# Sheet2.net
KiCad netlist of a schematic drawn in Altium Designer
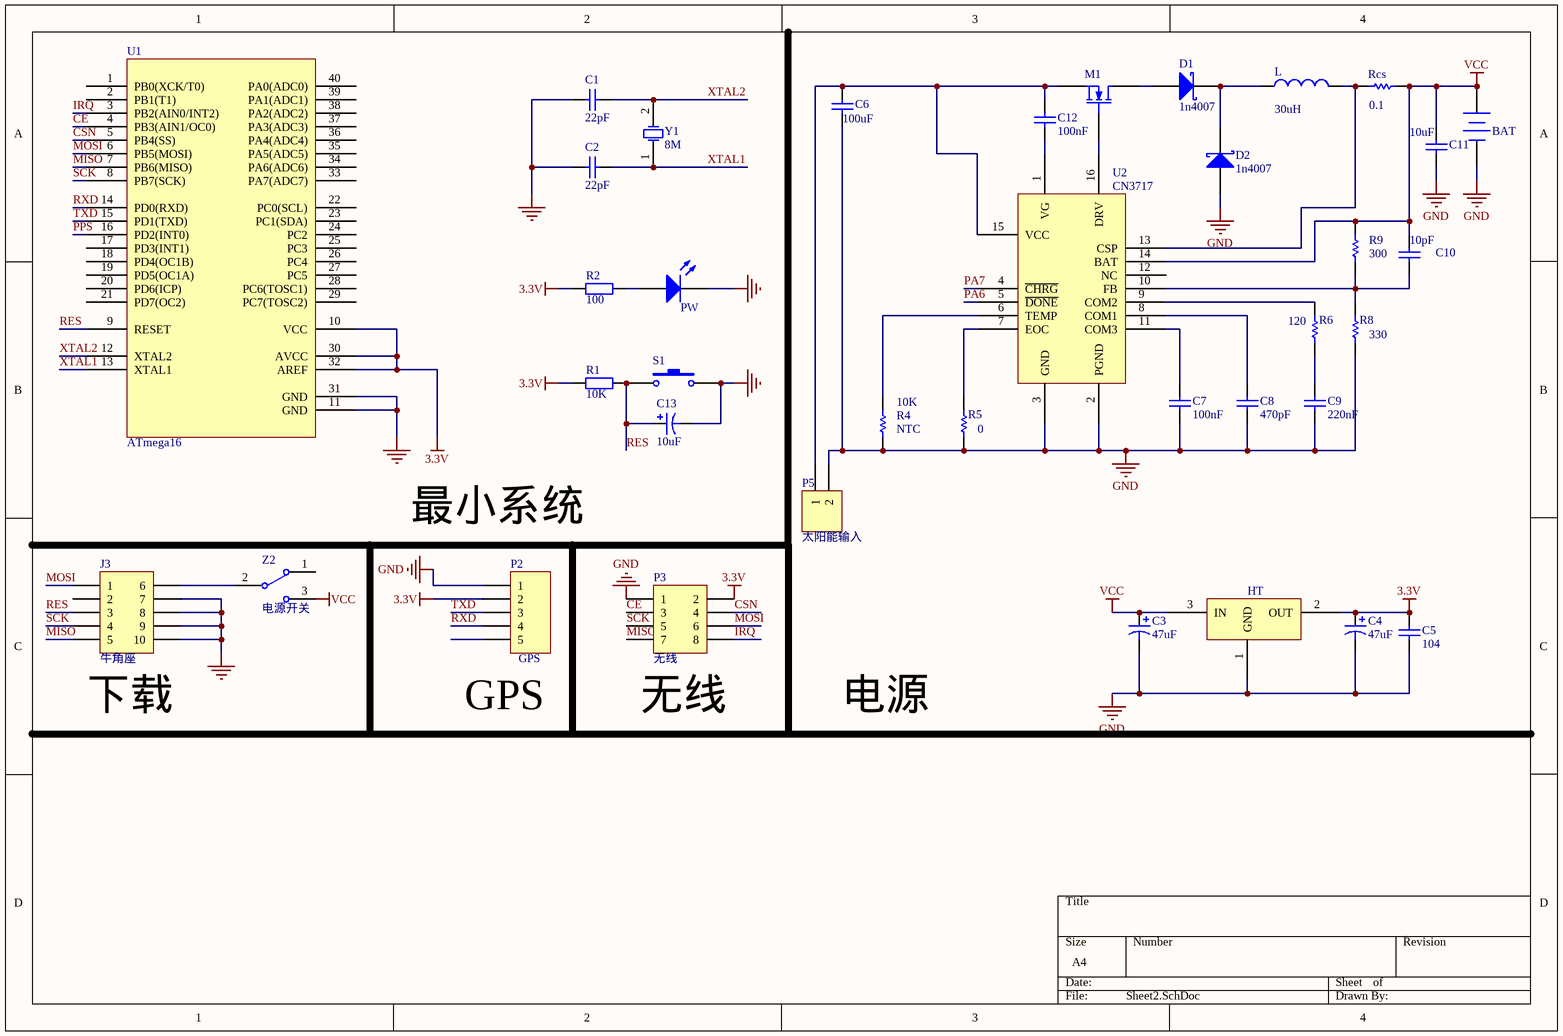
[diagram p0: Sheet2.SchDoc]

(export (version "E")
  (design (tool "Eeschema 10.0.6"))
  (components
    (comp (ref "1117_3.3V")
      (value "HT")
      (footprint "AMS1117-3.3V  SOT-223  贴片")
      (libsource (lib "Schlib1") (part "Component_1"))
    )
    (comp (ref "BAT")
      (value "Battery")
      (footprint "大2端子")
      (description "Multicell Battery")
      (fields (field (name "PUBLISHER") "Altium Limited"))
      (libsource (lib "Miscellaneous Devices") (part "Battery"))
    )
    (comp (ref "C1")
      (value "22pF")
      (footprint "电容CBB224(0.22)")
      (description "Capacitor")
      (fields (field (name "PUBLISHER") "Altium Limited"))
      (libsource (lib "Miscellaneous Devices") (part "Cap"))
    )
    (comp (ref "C2")
      (value "22pF")
      (footprint "电容CBB224(0.22)")
      (description "Capacitor")
      (fields (field (name "PUBLISHER") "Altium Limited"))
      (libsource (lib "Miscellaneous Devices") (part "Cap"))
    )
    (comp (ref "C3")
      (value "47uF")
      (footprint "电容")
      (description "Polarized Capacitor (Surface Mount)")
      (fields (field (name "PUBLISHER") "Altium Limited"))
      (libsource (lib "Miscellaneous Devices") (part "Cap Pol3"))
    )
    (comp (ref "C4")
      (value "47uF")
      (footprint "电容")
      (description "Polarized Capacitor (Surface Mount)")
      (fields (field (name "PUBLISHER") "Altium Limited"))
      (libsource (lib "Miscellaneous Devices") (part "Cap Pol3"))
    )
    (comp (ref "C5")
      (value "104")
      (footprint "电容CBB224(0.22)")
      (description "Capacitor")
      (fields (field (name "Comment") "Cap") (field (name "PUBLISHER") "Altium Limited"))
      (libsource (lib "Miscellaneous Devices") (part "Cap"))
    )
    (comp (ref "C6")
      (value "100uF")
      (footprint "电容CBB224(0.22)")
      (description "Capacitor")
      (fields (field (name "Comment") "Cap") (field (name "PUBLISHER") "Altium Limited"))
      (libsource (lib "Miscellaneous Devices") (part "Cap"))
    )
    (comp (ref "C7")
      (value "100nF")
      (footprint "电容CBB224(0.22)")
      (description "Capacitor")
      (fields (field (name "Comment") "Cap") (field (name "PUBLISHER") "Altium Limited"))
      (libsource (lib "Miscellaneous Devices") (part "Cap"))
    )
    (comp (ref "C8")
      (value "470pF")
      (footprint "电容CBB224(0.22)")
      (description "Capacitor")
      (fields (field (name "Comment") "Cap") (field (name "PUBLISHER") "Altium Limited"))
      (libsource (lib "Miscellaneous Devices") (part "Cap"))
    )
    (comp (ref "C9")
      (value "220nF")
      (footprint "电容CBB224(0.22)")
      (description "Capacitor")
      (fields (field (name "Comment") "Cap") (field (name "PUBLISHER") "Altium Limited"))
      (libsource (lib "Miscellaneous Devices") (part "Cap"))
    )
    (comp (ref "C10")
      (value "10pF")
      (footprint "电容CBB224(0.22)")
      (description "Capacitor")
      (fields (field (name "Comment") "Cap") (field (name "PUBLISHER") "Altium Limited"))
      (libsource (lib "Miscellaneous Devices") (part "Cap"))
    )
    (comp (ref "C11")
      (value "10uF")
      (footprint "电容CBB224(0.22)")
      (description "Capacitor")
      (fields (field (name "Comment") "Cap") (field (name "PUBLISHER") "Altium Limited"))
      (libsource (lib "Miscellaneous Devices") (part "Cap"))
    )
    (comp (ref "C12")
      (value "100nF")
      (footprint "电容CBB224(0.22)")
      (description "Capacitor")
      (fields (field (name "Comment") "Cap") (field (name "PUBLISHER") "Altium Limited"))
      (libsource (lib "Miscellaneous Devices") (part "Cap"))
    )
    (comp (ref "C13")
      (value "10uF")
      (footprint "电容")
      (description "Polarized Capacitor (Surface Mount)")
      (fields (field (name "PUBLISHER") "Altium Limited"))
      (libsource (lib "Miscellaneous Devices") (part "Cap Pol3"))
    )
    (comp (ref "D1")
      (value "1n4007")
      (footprint "稳压二极管")
      (description "Schottky Diode")
      (fields (field (name "PUBLISHER") "Altium Limited"))
      (libsource (lib "Miscellaneous Devices") (part "D Schottky"))
    )
    (comp (ref "D2")
      (value "1n4007")
      (footprint "稳压二极管")
      (description "Schottky Diode")
      (fields (field (name "PUBLISHER") "Altium Limited"))
      (libsource (lib "Miscellaneous Devices") (part "D Schottky"))
    )
    (comp (ref "J3")
      (value "牛角座")
      (footprint "下载口（12345）")
      (description "Header, 5-Pin, Dual row")
      (fields (field (name "PUBLISHER") "Altium Limited"))
      (libsource (lib "Miscellaneous Connectors") (part "Header 5X2A"))
    )
    (comp (ref "L")
      (value "30uH")
      (footprint "电感 直插")
      (description "Inductor")
      (fields (field (name "PUBLISHER") "Altium Limited"))
      (libsource (lib "Miscellaneous Devices") (part "Inductor"))
    )
    (comp (ref "M1")
      (value "MOSFET-N")
      (footprint "MOS管 贴片")
      (description "N-Channel MOSFET")
      (fields (field (name "PUBLISHER") "Altium Limited"))
      (libsource (lib "Miscellaneous Devices") (part "MOSFET-N"))
    )
    (comp (ref "P2")
      (value "GPS")
      (footprint "GPS模块")
      (description "Header, 5-Pin")
      (fields (field (name "PUBLISHER") "Altium Limited"))
      (libsource (lib "Miscellaneous Connectors") (part "Header 5"))
    )
    (comp (ref "P3")
      (value "无线")
      (footprint "无线模块")
      (description "Header, 4-Pin, Dual row")
      (fields (field (name "PUBLISHER") "Altium Limited"))
      (libsource (lib "Miscellaneous Connectors") (part "Header 4X2"))
    )
    (comp (ref "P5")
      (value "太阳能输入")
      (footprint "大2端子")
      (description "Header, 2-Pin")
      (fields (field (name "PUBLISHER") "Altium Limited"))
      (libsource (lib "Miscellaneous Connectors") (part "Header 2"))
    )
    (comp (ref "PW")
      (value "~")
      (footprint "LED")
      (description "Typical INFRARED GaAs LED")
      (fields (field (name "PUBLISHER") "Altium Limited"))
      (libsource (lib "Miscellaneous Devices") (part "LED0"))
    )
    (comp (ref "R1")
      (value "10K")
      (footprint "0805")
      (description "Resistor")
      (fields (field (name "PUBLISHER") "Altium Limited"))
      (libsource (lib "Miscellaneous Devices") (part "Res2"))
    )
    (comp (ref "R2")
      (value "100")
      (footprint "0805")
      (description "Resistor")
      (fields (field (name "PUBLISHER") "Altium Limited"))
      (libsource (lib "Miscellaneous Devices") (part "Res2"))
    )
    (comp (ref "R4")
      (value "NTC")
      (footprint "1206")
      (description "Resistor")
      (fields (field (name "ALTIUM_VALUE") "10K") (field (name "PUBLISHER") "Altium Limited"))
      (libsource (lib "Miscellaneous Devices") (part "Res1"))
    )
    (comp (ref "R5")
      (value "0")
      (footprint "1206")
      (description "Resistor")
      (fields (field (name "Comment") "Res1") (field (name "PUBLISHER") "Altium Limited"))
      (libsource (lib "Miscellaneous Devices") (part "Res1"))
    )
    (comp (ref "R6")
      (value "120")
      (footprint "0805")
      (description "Resistor")
      (fields (field (name "Comment") "Res1") (field (name "PUBLISHER") "Altium Limited"))
      (libsource (lib "Miscellaneous Devices") (part "Res1"))
    )
    (comp (ref "R8")
      (value "330")
      (footprint "0805")
      (description "Resistor")
      (fields (field (name "Comment") "Res1") (field (name "PUBLISHER") "Altium Limited"))
      (libsource (lib "Miscellaneous Devices") (part "Res1"))
    )
    (comp (ref "R9")
      (value "300")
      (footprint "0805")
      (description "Resistor")
      (fields (field (name "Comment") "Res1") (field (name "PUBLISHER") "Altium Limited"))
      (libsource (lib "Miscellaneous Devices") (part "Res1"))
    )
    (comp (ref "Rcs")
      (value "0.1")
      (footprint "2512 贴片")
      (description "Resistor")
      (fields (field (name "Comment") "Res1") (field (name "PUBLISHER") "Altium Limited"))
      (libsource (lib "Miscellaneous Devices") (part "Res1"))
    )
    (comp (ref "S1")
      (value "~")
      (footprint "4脚按键")
      (description "Switch")
      (fields (field (name "PUBLISHER") "Altium Limited"))
      (libsource (lib "Miscellaneous Devices") (part "SW-PB"))
    )
    (comp (ref "U1")
      (value "ATmega16")
      (footprint "DIP 40 单片机")
      (libsource (lib "Schlib1") (part "Component_2"))
    )
    (comp (ref "U2") (value "CN3717") (footprint "CN3717 贴片") (libsource (lib "Schlib1") (part "CN3717")))
    (comp (ref "Y1")
      (value "8M")
      (footprint "晶振")
      (description "Crystal Oscillator")
      (fields (field (name "PUBLISHER") "Altium Limited"))
      (libsource (lib "Miscellaneous Devices") (part "XTAL"))
    )
    (comp (ref "Z2")
      (value "电源开关")
      (footprint "自锁开关")
      (description "SPDT Subminiature Toggle Switch, Right Angle Mounting, Vertical Actuation")
      (fields (field (name "PUBLISHER") "Altium Limited"))
      (libsource (lib "Miscellaneous Devices") (part "SW-SPDT"))
    )
  )
  (nets
    (net (code "1") (name "/CE") (class "Default")
      (node (ref "P3") (pin "3") (pinfunction "3_3") (pintype "passive"))
      (node (ref "U1") (pin "4") (pinfunction "PB3(AIN1/OC0)_4") (pintype "passive"))
    )
    (net (code "2") (name "/CSN") (class "Default")
      (node (ref "P3") (pin "4") (pinfunction "4_4") (pintype "passive"))
      (node (ref "U1") (pin "5") (pinfunction "PB4(SS)_5") (pintype "passive"))
    )
    (net (code "3") (name "/IRQ") (class "Default")
      (node (ref "P3") (pin "8") (pinfunction "8_8") (pintype "passive"))
      (node (ref "U1") (pin "3") (pinfunction "PB2(AIN0/INT2)_3") (pintype "passive"))
    )
    (net (code "4") (name "/MISO") (class "Default")
      (node (ref "J3") (pin "5") (pinfunction "5_5") (pintype "passive"))
      (node (ref "P3") (pin "7") (pinfunction "7_7") (pintype "passive"))
      (node (ref "U1") (pin "7") (pinfunction "PB6(MISO)_7") (pintype "passive"))
    )
    (net (code "5") (name "/MOSI") (class "Default")
      (node (ref "J3") (pin "1") (pinfunction "1_1") (pintype "passive"))
      (node (ref "P3") (pin "6") (pinfunction "6_6") (pintype "passive"))
      (node (ref "U1") (pin "6") (pinfunction "PB5(MOSI)_6") (pintype "passive"))
    )
    (net (code "6") (name "/PA6") (class "Default")
      (node (ref "U2") (pin "5") (pinfunction "~{DONE}_5") (pintype "passive"))
    )
    (net (code "7") (name "/PA7") (class "Default")
      (node (ref "U2") (pin "4") (pinfunction "~{CHRG}_4") (pintype "passive"))
    )
    (net (code "8") (name "/PPS") (class "Default")
      (node (ref "U1") (pin "16") (pinfunction "PD2(INT0)_16") (pintype "passive"))
    )
    (net (code "9") (name "/RES") (class "Default")
      (node (ref "C13") (pin "1") (pinfunction "1_1") (pintype "passive"))
      (node (ref "J3") (pin "3") (pinfunction "3_3") (pintype "passive"))
      (node (ref "R1") (pin "2") (pinfunction "2_2") (pintype "passive"))
      (node (ref "S1") (pin "1") (pinfunction "1_1") (pintype "passive"))
      (node (ref "U1") (pin "9") (pinfunction "RESET_9") (pintype "passive"))
    )
    (net (code "10") (name "/RXD") (class "Default")
      (node (ref "P2") (pin "4") (pinfunction "4_4") (pintype "passive"))
      (node (ref "U1") (pin "14") (pinfunction "PD0(RXD)_14") (pintype "passive"))
    )
    (net (code "11") (name "/SCK") (class "Default")
      (node (ref "J3") (pin "4") (pinfunction "4_4") (pintype "passive"))
      (node (ref "P3") (pin "5") (pinfunction "5_5") (pintype "passive"))
      (node (ref "U1") (pin "8") (pinfunction "PB7(SCK)_8") (pintype "passive"))
    )
    (net (code "12") (name "/TXD") (class "Default")
      (node (ref "P2") (pin "3") (pinfunction "3_3") (pintype "passive"))
      (node (ref "U1") (pin "15") (pinfunction "PD1(TXD)_15") (pintype "passive"))
    )
    (net (code "13") (name "/XTAL1") (class "Default")
      (node (ref "C2") (pin "2") (pinfunction "2_2") (pintype "passive"))
      (node (ref "U1") (pin "13") (pinfunction "XTAL1_13") (pintype "passive"))
      (node (ref "Y1") (pin "1") (pinfunction "OSC1_1") (pintype "passive"))
    )
    (net (code "14") (name "/XTAL2") (class "Default")
      (node (ref "C1") (pin "2") (pinfunction "2_2") (pintype "passive"))
      (node (ref "U1") (pin "12") (pinfunction "XTAL2_12") (pintype "passive"))
      (node (ref "Y1") (pin "2") (pinfunction "OSC2_2") (pintype "passive"))
    )
    (net (code "15") (name "3.3V") (class "Default")
      (node (ref "1117_3.3V") (pin "2") (pinfunction "OUT_2") (pintype "passive"))
      (node (ref "C4") (pin "1") (pinfunction "1_1") (pintype "passive"))
      (node (ref "C5") (pin "1") (pinfunction "1_1") (pintype "passive"))
      (node (ref "P2") (pin "2") (pinfunction "2_2") (pintype "passive"))
      (node (ref "P3") (pin "2") (pinfunction "2_2") (pintype "passive"))
      (node (ref "R1") (pin "1") (pinfunction "1_1") (pintype "passive"))
      (node (ref "R2") (pin "1") (pinfunction "1_1") (pintype "passive"))
      (node (ref "U1") (pin "10") (pinfunction "VCC_10") (pintype "passive"))
      (node (ref "U1") (pin "30") (pinfunction "AVCC_30") (pintype "passive"))
      (node (ref "U1") (pin "32") (pinfunction "AREF_32") (pintype "passive"))
    )
    (net (code "16") (name "GND") (class "Default")
      (node (ref "1117_3.3V") (pin "1") (pinfunction "GND_1") (pintype "passive"))
      (node (ref "BAT") (pin "2") (pinfunction "-_2") (pintype "passive"))
      (node (ref "C1") (pin "1") (pinfunction "1_1") (pintype "passive"))
      (node (ref "C11") (pin "1") (pinfunction "1_1") (pintype "passive"))
      (node (ref "C13") (pin "2") (pinfunction "2_2") (pintype "passive"))
      (node (ref "C2") (pin "1") (pinfunction "1_1") (pintype "passive"))
      (node (ref "C3") (pin "2") (pinfunction "2_2") (pintype "passive"))
      (node (ref "C4") (pin "2") (pinfunction "2_2") (pintype "passive"))
      (node (ref "C5") (pin "2") (pinfunction "2_2") (pintype "passive"))
      (node (ref "C6") (pin "1") (pinfunction "1_1") (pintype "passive"))
      (node (ref "C7") (pin "1") (pinfunction "1_1") (pintype "passive"))
      (node (ref "C8") (pin "1") (pinfunction "1_1") (pintype "passive"))
      (node (ref "C9") (pin "1") (pinfunction "1_1") (pintype "passive"))
      (node (ref "D2") (pin "1") (pinfunction "A_1") (pintype "passive"))
      (node (ref "J3") (pin "10") (pinfunction "10_10") (pintype "passive"))
      (node (ref "J3") (pin "7") (pinfunction "7_7") (pintype "passive"))
      (node (ref "J3") (pin "8") (pinfunction "8_8") (pintype "passive"))
      (node (ref "J3") (pin "9") (pinfunction "9_9") (pintype "passive"))
      (node (ref "P2") (pin "1") (pinfunction "1_1") (pintype "passive"))
      (node (ref "P3") (pin "1") (pinfunction "1_1") (pintype "passive"))
      (node (ref "P5") (pin "2") (pinfunction "2_2") (pintype "passive"))
      (node (ref "PW") (pin "2") (pinfunction "K_2") (pintype "passive"))
      (node (ref "R4") (pin "1") (pinfunction "1_1") (pintype "passive"))
      (node (ref "R5") (pin "1") (pinfunction "1_1") (pintype "passive"))
      (node (ref "R8") (pin "1") (pinfunction "1_1") (pintype "passive"))
      (node (ref "S1") (pin "2") (pinfunction "2_2") (pintype "passive"))
      (node (ref "U1") (pin "11") (pinfunction "GND_11") (pintype "passive"))
      (node (ref "U1") (pin "31") (pinfunction "GND_31") (pintype "passive"))
      (node (ref "U2") (pin "2") (pinfunction "PGND_2") (pintype "passive"))
      (node (ref "U2") (pin "3") (pinfunction "GND_3") (pintype "passive"))
    )
    (net (code "17") (name "Net-(C9-Pad2)") (class "Default")
      (node (ref "C9") (pin "2") (pinfunction "2_2") (pintype "passive"))
      (node (ref "R6") (pin "1") (pinfunction "1_1") (pintype "passive"))
    )
    (net (code "18") (name "Net-(D1-A)") (class "Default")
      (node (ref "D1") (pin "1") (pinfunction "A_1") (pintype "passive"))
      (node (ref "M1") (pin "1") (pinfunction "D_1") (pintype "passive"))
    )
    (net (code "19") (name "Net-(D1-K)") (class "Default")
      (node (ref "D1") (pin "2") (pinfunction "K_2") (pintype "passive"))
      (node (ref "D2") (pin "2") (pinfunction "K_2") (pintype "passive"))
      (node (ref "L") (pin "1") (pinfunction "1_1") (pintype "passive"))
    )
    (net (code "20") (name "Net-(J3-Pad6)") (class "Default")
      (node (ref "J3") (pin "6") (pinfunction "6_6") (pintype "passive"))
      (node (ref "Z2") (pin "2") (pinfunction "2_2") (pintype "passive"))
    )
    (net (code "21") (name "Net-(M1-G)") (class "Default")
      (node (ref "M1") (pin "2") (pinfunction "G_2") (pintype "passive"))
      (node (ref "U2") (pin "16") (pinfunction "DRV_16") (pintype "passive"))
    )
    (net (code "22") (name "Net-(M1-S)") (class "Default")
      (node (ref "C12") (pin "2") (pinfunction "2_2") (pintype "passive"))
      (node (ref "C6") (pin "2") (pinfunction "2_2") (pintype "passive"))
      (node (ref "M1") (pin "3") (pinfunction "S_3") (pintype "passive"))
      (node (ref "P5") (pin "1") (pinfunction "1_1") (pintype "passive"))
      (node (ref "U2") (pin "15") (pinfunction "VCC_15") (pintype "passive"))
    )
    (net (code "23") (name "Net-(PW-A)") (class "Default")
      (node (ref "PW") (pin "1") (pinfunction "A_1") (pintype "passive"))
      (node (ref "R2") (pin "2") (pinfunction "2_2") (pintype "passive"))
    )
    (net (code "24") (name "Net-(U2-COM1)") (class "Default")
      (node (ref "C8") (pin "2") (pinfunction "2_2") (pintype "passive"))
      (node (ref "U2") (pin "8") (pinfunction "COM1_8") (pintype "passive"))
    )
    (net (code "25") (name "Net-(U2-COM2)") (class "Default")
      (node (ref "R6") (pin "2") (pinfunction "2_2") (pintype "passive"))
      (node (ref "U2") (pin "9") (pinfunction "COM2_9") (pintype "passive"))
    )
    (net (code "26") (name "Net-(U2-COM3)") (class "Default")
      (node (ref "C7") (pin "2") (pinfunction "2_2") (pintype "passive"))
      (node (ref "U2") (pin "11") (pinfunction "COM3_11") (pintype "passive"))
    )
    (net (code "27") (name "Net-(U2-CSP)") (class "Default")
      (node (ref "L") (pin "2") (pinfunction "2_2") (pintype "passive"))
      (node (ref "Rcs") (pin "1") (pinfunction "1_1") (pintype "passive"))
      (node (ref "U2") (pin "13") (pinfunction "CSP_13") (pintype "passive"))
    )
    (net (code "28") (name "Net-(U2-EOC)") (class "Default")
      (node (ref "R5") (pin "2") (pinfunction "2_2") (pintype "passive"))
      (node (ref "U2") (pin "7") (pinfunction "EOC_7") (pintype "passive"))
    )
    (net (code "29") (name "Net-(U2-FB)") (class "Default")
      (node (ref "C10") (pin "1") (pinfunction "1_1") (pintype "passive"))
      (node (ref "R8") (pin "2") (pinfunction "2_2") (pintype "passive"))
      (node (ref "R9") (pin "1") (pinfunction "1_1") (pintype "passive"))
      (node (ref "U2") (pin "10") (pinfunction "FB_10") (pintype "passive"))
    )
    (net (code "30") (name "Net-(U2-TEMP)") (class "Default")
      (node (ref "R4") (pin "2") (pinfunction "2_2") (pintype "passive"))
      (node (ref "U2") (pin "6") (pinfunction "TEMP_6") (pintype "passive"))
    )
    (net (code "31") (name "Net-(U2-VG)") (class "Default")
      (node (ref "C12") (pin "1") (pinfunction "1_1") (pintype "passive"))
      (node (ref "U2") (pin "1") (pinfunction "VG_1") (pintype "passive"))
    )
    (net (code "32") (name "VCC") (class "Default")
      (node (ref "1117_3.3V") (pin "3") (pinfunction "IN_3") (pintype "passive"))
      (node (ref "BAT") (pin "1") (pinfunction "+_1") (pintype "passive"))
      (node (ref "C10") (pin "2") (pinfunction "2_2") (pintype "passive"))
      (node (ref "C11") (pin "2") (pinfunction "2_2") (pintype "passive"))
      (node (ref "C3") (pin "1") (pinfunction "1_1") (pintype "passive"))
      (node (ref "R9") (pin "2") (pinfunction "2_2") (pintype "passive"))
      (node (ref "Rcs") (pin "2") (pinfunction "2_2") (pintype "passive"))
      (node (ref "U2") (pin "14") (pinfunction "BAT_14") (pintype "passive"))
      (node (ref "Z2") (pin "3") (pinfunction "3_3") (pintype "passive"))
    )
    (net (code "33") (name "unconnected-(J3-Pad2)") (class "Default")
      (node (ref "J3") (pin "2") (pinfunction "2_2") (pintype "passive"))
    )
    (net (code "34") (name "unconnected-(P2-Pad5)") (class "Default")
      (node (ref "P2") (pin "5") (pinfunction "5_5") (pintype "passive"))
    )
    (net (code "35") (name "unconnected-(U1-PA0(ADC0)-Pad40)") (class "Default")
      (node (ref "U1") (pin "40") (pinfunction "PA0(ADC0)_40") (pintype "passive"))
    )
    (net (code "36") (name "unconnected-(U1-PA1(ADC1)-Pad39)") (class "Default")
      (node (ref "U1") (pin "39") (pinfunction "PA1(ADC1)_39") (pintype "passive"))
    )
    (net (code "37") (name "unconnected-(U1-PA2(ADC2)-Pad38)") (class "Default")
      (node (ref "U1") (pin "38") (pinfunction "PA2(ADC2)_38") (pintype "passive"))
    )
    (net (code "38") (name "unconnected-(U1-PA3(ADC3)-Pad37)") (class "Default")
      (node (ref "U1") (pin "37") (pinfunction "PA3(ADC3)_37") (pintype "passive"))
    )
    (net (code "39") (name "unconnected-(U1-PA4(ADC4)-Pad36)") (class "Default")
      (node (ref "U1") (pin "36") (pinfunction "PA4(ADC4)_36") (pintype "passive"))
    )
    (net (code "40") (name "unconnected-(U1-PA5(ADC5)-Pad35)") (class "Default")
      (node (ref "U1") (pin "35") (pinfunction "PA5(ADC5)_35") (pintype "passive"))
    )
    (net (code "41") (name "unconnected-(U1-PA6(ADC6)-Pad34)") (class "Default")
      (node (ref "U1") (pin "34") (pinfunction "PA6(ADC6)_34") (pintype "passive"))
    )
    (net (code "42") (name "unconnected-(U1-PA7(ADC7)-Pad33)") (class "Default")
      (node (ref "U1") (pin "33") (pinfunction "PA7(ADC7)_33") (pintype "passive"))
    )
    (net (code "43") (name "unconnected-(U1-PB0(XCK{slash}T0)-Pad1)") (class "Default")
      (node (ref "U1") (pin "1") (pinfunction "PB0(XCK/T0)_1") (pintype "passive"))
    )
    (net (code "44") (name "unconnected-(U1-PB1(T1)-Pad2)") (class "Default")
      (node (ref "U1") (pin "2") (pinfunction "PB1(T1)_2") (pintype "passive"))
    )
    (net (code "45") (name "unconnected-(U1-PC0(SCL)-Pad22)") (class "Default")
      (node (ref "U1") (pin "22") (pinfunction "PC0(SCL)_22") (pintype "passive"))
    )
    (net (code "46") (name "unconnected-(U1-PC1(SDA)-Pad23)") (class "Default")
      (node (ref "U1") (pin "23") (pinfunction "PC1(SDA)_23") (pintype "passive"))
    )
    (net (code "47") (name "unconnected-(U1-PC2-Pad24)") (class "Default")
      (node (ref "U1") (pin "24") (pinfunction "PC2_24") (pintype "passive"))
    )
    (net (code "48") (name "unconnected-(U1-PC3-Pad25)") (class "Default")
      (node (ref "U1") (pin "25") (pinfunction "PC3_25") (pintype "passive"))
    )
    (net (code "49") (name "unconnected-(U1-PC4-Pad26)") (class "Default")
      (node (ref "U1") (pin "26") (pinfunction "PC4_26") (pintype "passive"))
    )
    (net (code "50") (name "unconnected-(U1-PC5-Pad27)") (class "Default")
      (node (ref "U1") (pin "27") (pinfunction "PC5_27") (pintype "passive"))
    )
    (net (code "51") (name "unconnected-(U1-PC6(TOSC1)-Pad28)") (class "Default")
      (node (ref "U1") (pin "28") (pinfunction "PC6(TOSC1)_28") (pintype "passive"))
    )
    (net (code "52") (name "unconnected-(U1-PC7(TOSC2)-Pad29)") (class "Default")
      (node (ref "U1") (pin "29") (pinfunction "PC7(TOSC2)_29") (pintype "passive"))
    )
    (net (code "53") (name "unconnected-(U1-PD3(INT1)-Pad17)") (class "Default")
      (node (ref "U1") (pin "17") (pinfunction "PD3(INT1)_17") (pintype "passive"))
    )
    (net (code "54") (name "unconnected-(U1-PD4(OC1B)-Pad18)") (class "Default")
      (node (ref "U1") (pin "18") (pinfunction "PD4(OC1B)_18") (pintype "passive"))
    )
    (net (code "55") (name "unconnected-(U1-PD5(OC1A)-Pad19)") (class "Default")
      (node (ref "U1") (pin "19") (pinfunction "PD5(OC1A)_19") (pintype "passive"))
    )
    (net (code "56") (name "unconnected-(U1-PD6(ICP)-Pad20)") (class "Default")
      (node (ref "U1") (pin "20") (pinfunction "PD6(ICP)_20") (pintype "passive"))
    )
    (net (code "57") (name "unconnected-(U1-PD7(OC2)-Pad21)") (class "Default")
      (node (ref "U1") (pin "21") (pinfunction "PD7(OC2)_21") (pintype "passive"))
    )
    (net (code "58") (name "unconnected-(U2-NC-Pad12)") (class "Default")
      (node (ref "U2") (pin "12") (pinfunction "NC_12") (pintype "passive"))
    )
    (net (code "59") (name "unconnected-(Z2-Pad1)") (class "Default")
      (node (ref "Z2") (pin "1") (pinfunction "1_1") (pintype "passive"))
    )
  )
)
